# 01-pushbutton_interface.net
KiCad netlist of a schematic drawn in EAGLE
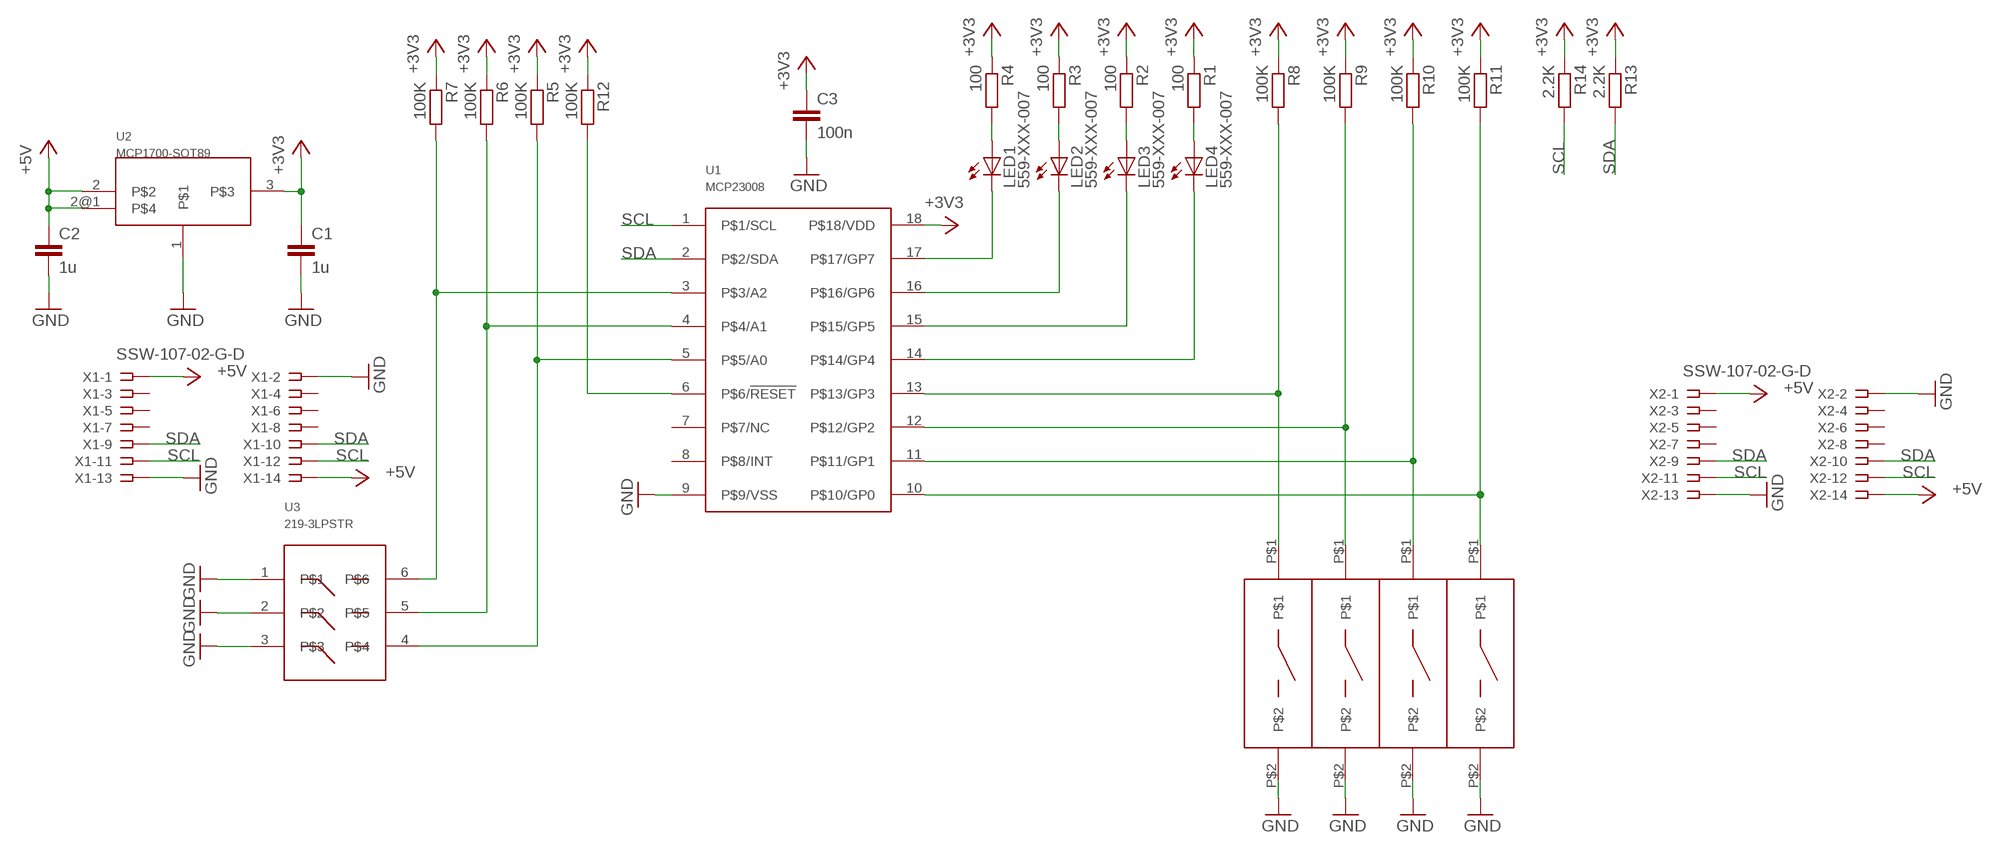
[diagram p0: schematic, sheet 1]

(export (version "E")
  (design (tool "Eeschema 10.0.6"))
  (components
    (comp (ref "C1")
      (value "1u")
      (footprint "eagle-import:C0805")
      (libsource (lib "eagle-import") (part "C-EUC0805"))
    )
    (comp (ref "C2")
      (value "1u")
      (footprint "eagle-import:C0805")
      (libsource (lib "eagle-import") (part "C-EUC0805"))
    )
    (comp (ref "C3")
      (value "100n")
      (footprint "eagle-import:C0805")
      (libsource (lib "eagle-import") (part "C-EUC0805"))
    )
    (comp (ref "LED1")
      (value "559-XXX-007")
      (footprint "eagle-import:LED")
      (libsource (lib "eagle-import") (part "559-XXX-007"))
    )
    (comp (ref "LED2")
      (value "559-XXX-007")
      (footprint "eagle-import:LED")
      (libsource (lib "eagle-import") (part "559-XXX-007"))
    )
    (comp (ref "LED3")
      (value "559-XXX-007")
      (footprint "eagle-import:LED")
      (libsource (lib "eagle-import") (part "559-XXX-007"))
    )
    (comp (ref "LED4")
      (value "559-XXX-007")
      (footprint "eagle-import:LED")
      (libsource (lib "eagle-import") (part "559-XXX-007"))
    )
    (comp (ref "R1")
      (value "100")
      (footprint "eagle-import:R0805")
      (libsource (lib "eagle-import") (part "R-EU_R0805"))
    )
    (comp (ref "R2")
      (value "100")
      (footprint "eagle-import:R0805")
      (libsource (lib "eagle-import") (part "R-EU_R0805"))
    )
    (comp (ref "R3")
      (value "100")
      (footprint "eagle-import:R0805")
      (libsource (lib "eagle-import") (part "R-EU_R0805"))
    )
    (comp (ref "R4")
      (value "100")
      (footprint "eagle-import:R0805")
      (libsource (lib "eagle-import") (part "R-EU_R0805"))
    )
    (comp (ref "R5")
      (value "100K")
      (footprint "eagle-import:R0805")
      (libsource (lib "eagle-import") (part "R-EU_R0805"))
    )
    (comp (ref "R6")
      (value "100K")
      (footprint "eagle-import:R0805")
      (libsource (lib "eagle-import") (part "R-EU_R0805"))
    )
    (comp (ref "R7")
      (value "100K")
      (footprint "eagle-import:R0805")
      (libsource (lib "eagle-import") (part "R-EU_R0805"))
    )
    (comp (ref "R8")
      (value "100K")
      (footprint "eagle-import:R0805")
      (libsource (lib "eagle-import") (part "R-EU_R0805"))
    )
    (comp (ref "R9")
      (value "100K")
      (footprint "eagle-import:R0805")
      (libsource (lib "eagle-import") (part "R-EU_R0805"))
    )
    (comp (ref "R10")
      (value "100K")
      (footprint "eagle-import:R0805")
      (libsource (lib "eagle-import") (part "R-EU_R0805"))
    )
    (comp (ref "R11")
      (value "100K")
      (footprint "eagle-import:R0805")
      (libsource (lib "eagle-import") (part "R-EU_R0805"))
    )
    (comp (ref "R12")
      (value "100K")
      (footprint "eagle-import:R0805")
      (libsource (lib "eagle-import") (part "R-EU_R0805"))
    )
    (comp (ref "R13")
      (value "2.2K")
      (footprint "eagle-import:R0805")
      (libsource (lib "eagle-import") (part "R-EU_R0805"))
    )
    (comp (ref "R14")
      (value "2.2K")
      (footprint "eagle-import:R0805")
      (libsource (lib "eagle-import") (part "R-EU_R0805"))
    )
    (comp (ref "SW1")
      (value "PB-SWITCH")
      (footprint "eagle-import:SWITCH")
      (libsource (lib "eagle-import") (part "PB-SWITCH"))
    )
    (comp (ref "SW2")
      (value "PB-SWITCH")
      (footprint "eagle-import:SWITCH")
      (libsource (lib "eagle-import") (part "PB-SWITCH"))
    )
    (comp (ref "SW3")
      (value "PB-SWITCH")
      (footprint "eagle-import:SWITCH")
      (libsource (lib "eagle-import") (part "PB-SWITCH"))
    )
    (comp (ref "SW4")
      (value "PB-SWITCH")
      (footprint "eagle-import:SWITCH")
      (libsource (lib "eagle-import") (part "PB-SWITCH"))
    )
    (comp (ref "U1")
      (value "MCP23008")
      (footprint "eagle-import:MCP23008-SO18")
      (libsource (lib "eagle-import") (part "MCP23008"))
    )
    (comp (ref "U2")
      (value "MCP1700-SOT89")
      (footprint "eagle-import:MCP1700-SOT89")
      (libsource (lib "eagle-import") (part "MCP1700-SOT89"))
    )
    (comp (ref "U3")
      (value "219-3LPSTR")
      (footprint "eagle-import:219-3LPSTR")
      (libsource (lib "eagle-import") (part "219-3LPSTR"))
    )
    (comp (ref "X1")
      (value "SSW-107-02-G-D")
      (footprint "eagle-import:SSW-107-02-G-D")
      (fields (field (name "MF") "Samtec Inc."))
      (libsource (lib "eagle-import") (part "SSW-107-02-G-D"))
    )
    (comp (ref "X2")
      (value "SSW-107-02-G-D")
      (footprint "eagle-import:SSW-107-02-G-D")
      (fields (field (name "MF") "Samtec Inc."))
      (libsource (lib "eagle-import") (part "SSW-107-02-G-D"))
    )
  )
  (nets
    (net (code "1") (name "+3V3") (class "Default")
      (node (ref "C1") (pin "1") (pinfunction "1_1") (pintype "passive"))
      (node (ref "C3") (pin "1") (pinfunction "1_1") (pintype "passive"))
      (node (ref "R1") (pin "1") (pinfunction "1_1") (pintype "passive"))
      (node (ref "R10") (pin "1") (pinfunction "1_1") (pintype "passive"))
      (node (ref "R11") (pin "1") (pinfunction "1_1") (pintype "passive"))
      (node (ref "R12") (pin "1") (pinfunction "1_1") (pintype "passive"))
      (node (ref "R13") (pin "1") (pinfunction "1_1") (pintype "passive"))
      (node (ref "R14") (pin "1") (pinfunction "1_1") (pintype "passive"))
      (node (ref "R2") (pin "1") (pinfunction "1_1") (pintype "passive"))
      (node (ref "R3") (pin "1") (pinfunction "1_1") (pintype "passive"))
      (node (ref "R4") (pin "1") (pinfunction "1_1") (pintype "passive"))
      (node (ref "R5") (pin "1") (pinfunction "1_1") (pintype "passive"))
      (node (ref "R6") (pin "1") (pinfunction "1_1") (pintype "passive"))
      (node (ref "R7") (pin "1") (pinfunction "1_1") (pintype "passive"))
      (node (ref "R8") (pin "1") (pinfunction "1_1") (pintype "passive"))
      (node (ref "R9") (pin "1") (pinfunction "1_1") (pintype "passive"))
      (node (ref "U1") (pin "18") (pinfunction "P$18/VDD_18") (pintype "bidirectional"))
      (node (ref "U2") (pin "3") (pinfunction "P$3_3") (pintype "bidirectional"))
    )
    (net (code "2") (name "+5V") (class "Default")
      (node (ref "C2") (pin "1") (pinfunction "1_1") (pintype "passive"))
      (node (ref "U2") (pin "2") (pinfunction "P$2_2") (pintype "bidirectional"))
      (node (ref "U2") (pin "2@1") (pinfunction "P$4_2@1") (pintype "bidirectional"))
      (node (ref "X1") (pin "1") (pinfunction "1_1") (pintype "passive"))
      (node (ref "X1") (pin "14") (pinfunction "1_14") (pintype "passive"))
      (node (ref "X2") (pin "1") (pinfunction "1_1") (pintype "passive"))
      (node (ref "X2") (pin "14") (pinfunction "1_14") (pintype "passive"))
    )
    (net (code "3") (name "/SCL") (class "Default")
      (node (ref "R14") (pin "2") (pinfunction "2_2") (pintype "passive"))
      (node (ref "U1") (pin "1") (pinfunction "P$1/SCL_1") (pintype "bidirectional"))
      (node (ref "X1") (pin "11") (pinfunction "1_11") (pintype "passive"))
      (node (ref "X1") (pin "12") (pinfunction "1_12") (pintype "passive"))
      (node (ref "X2") (pin "11") (pinfunction "1_11") (pintype "passive"))
      (node (ref "X2") (pin "12") (pinfunction "1_12") (pintype "passive"))
    )
    (net (code "4") (name "/SDA") (class "Default")
      (node (ref "R13") (pin "2") (pinfunction "2_2") (pintype "passive"))
      (node (ref "U1") (pin "2") (pinfunction "P$2/SDA_2") (pintype "bidirectional"))
      (node (ref "X1") (pin "10") (pinfunction "1_10") (pintype "passive"))
      (node (ref "X1") (pin "9") (pinfunction "1_9") (pintype "passive"))
      (node (ref "X2") (pin "10") (pinfunction "1_10") (pintype "passive"))
      (node (ref "X2") (pin "9") (pinfunction "1_9") (pintype "passive"))
    )
    (net (code "5") (name "GND") (class "Default")
      (node (ref "C1") (pin "2") (pinfunction "2_2") (pintype "passive"))
      (node (ref "C2") (pin "2") (pinfunction "2_2") (pintype "passive"))
      (node (ref "C3") (pin "2") (pinfunction "2_2") (pintype "passive"))
      (node (ref "SW1") (pin "P$2") (pinfunction "P$2_P$2") (pintype "bidirectional"))
      (node (ref "SW2") (pin "P$2") (pinfunction "P$2_P$2") (pintype "bidirectional"))
      (node (ref "SW3") (pin "P$2") (pinfunction "P$2_P$2") (pintype "bidirectional"))
      (node (ref "SW4") (pin "P$2") (pinfunction "P$2_P$2") (pintype "bidirectional"))
      (node (ref "U1") (pin "9") (pinfunction "P$9/VSS_9") (pintype "bidirectional"))
      (node (ref "U2") (pin "1") (pinfunction "P$1_1") (pintype "bidirectional"))
      (node (ref "U3") (pin "1") (pinfunction "P$1_1") (pintype "bidirectional"))
      (node (ref "U3") (pin "2") (pinfunction "P$2_2") (pintype "bidirectional"))
      (node (ref "U3") (pin "3") (pinfunction "P$3_3") (pintype "bidirectional"))
      (node (ref "X1") (pin "13") (pinfunction "1_13") (pintype "passive"))
      (node (ref "X1") (pin "2") (pinfunction "1_2") (pintype "passive"))
      (node (ref "X2") (pin "13") (pinfunction "1_13") (pintype "passive"))
      (node (ref "X2") (pin "2") (pinfunction "1_2") (pintype "passive"))
    )
    (net (code "6") (name "Net-(LED1-A)") (class "Default")
      (node (ref "LED1") (pin "P$1") (pinfunction "A_P$1") (pintype "passive"))
      (node (ref "R4") (pin "2") (pinfunction "2_2") (pintype "passive"))
    )
    (net (code "7") (name "Net-(LED1-C)") (class "Default")
      (node (ref "LED1") (pin "P$2") (pinfunction "C_P$2") (pintype "passive"))
      (node (ref "U1") (pin "17") (pinfunction "P$17/GP7_17") (pintype "bidirectional"))
    )
    (net (code "8") (name "Net-(LED2-A)") (class "Default")
      (node (ref "LED2") (pin "P$1") (pinfunction "A_P$1") (pintype "passive"))
      (node (ref "R3") (pin "2") (pinfunction "2_2") (pintype "passive"))
    )
    (net (code "9") (name "Net-(LED2-C)") (class "Default")
      (node (ref "LED2") (pin "P$2") (pinfunction "C_P$2") (pintype "passive"))
      (node (ref "U1") (pin "16") (pinfunction "P$16/GP6_16") (pintype "bidirectional"))
    )
    (net (code "10") (name "Net-(LED3-A)") (class "Default")
      (node (ref "LED3") (pin "P$1") (pinfunction "A_P$1") (pintype "passive"))
      (node (ref "R2") (pin "2") (pinfunction "2_2") (pintype "passive"))
    )
    (net (code "11") (name "Net-(LED3-C)") (class "Default")
      (node (ref "LED3") (pin "P$2") (pinfunction "C_P$2") (pintype "passive"))
      (node (ref "U1") (pin "15") (pinfunction "P$15/GP5_15") (pintype "bidirectional"))
    )
    (net (code "12") (name "Net-(LED4-A)") (class "Default")
      (node (ref "LED4") (pin "P$1") (pinfunction "A_P$1") (pintype "passive"))
      (node (ref "R1") (pin "2") (pinfunction "2_2") (pintype "passive"))
    )
    (net (code "13") (name "Net-(LED4-C)") (class "Default")
      (node (ref "LED4") (pin "P$2") (pinfunction "C_P$2") (pintype "passive"))
      (node (ref "U1") (pin "14") (pinfunction "P$14/GP4_14") (pintype "bidirectional"))
    )
    (net (code "14") (name "Net-(U1-P$3{slash}A2)") (class "Default")
      (node (ref "R7") (pin "2") (pinfunction "2_2") (pintype "passive"))
      (node (ref "U1") (pin "3") (pinfunction "P$3/A2_3") (pintype "bidirectional"))
      (node (ref "U3") (pin "6") (pinfunction "P$6_6") (pintype "bidirectional"))
    )
    (net (code "15") (name "Net-(U1-P$4{slash}A1)") (class "Default")
      (node (ref "R6") (pin "2") (pinfunction "2_2") (pintype "passive"))
      (node (ref "U1") (pin "4") (pinfunction "P$4/A1_4") (pintype "bidirectional"))
      (node (ref "U3") (pin "5") (pinfunction "P$5_5") (pintype "bidirectional"))
    )
    (net (code "16") (name "Net-(U1-P$5{slash}A0)") (class "Default")
      (node (ref "R5") (pin "2") (pinfunction "2_2") (pintype "passive"))
      (node (ref "U1") (pin "5") (pinfunction "P$5/A0_5") (pintype "bidirectional"))
      (node (ref "U3") (pin "4") (pinfunction "P$4_4") (pintype "bidirectional"))
    )
    (net (code "17") (name "Net-(U1-P$6{slash}~{RESET})") (class "Default")
      (node (ref "R12") (pin "2") (pinfunction "2_2") (pintype "passive"))
      (node (ref "U1") (pin "6") (pinfunction "P$6/~{RESET}_6") (pintype "bidirectional"))
    )
    (net (code "18") (name "Net-(U1-P$10{slash}GP0)") (class "Default")
      (node (ref "R11") (pin "2") (pinfunction "2_2") (pintype "passive"))
      (node (ref "SW4") (pin "P$1") (pinfunction "P$1_P$1") (pintype "bidirectional"))
      (node (ref "U1") (pin "10") (pinfunction "P$10/GP0_10") (pintype "bidirectional"))
    )
    (net (code "19") (name "Net-(U1-P$11{slash}GP1)") (class "Default")
      (node (ref "R10") (pin "2") (pinfunction "2_2") (pintype "passive"))
      (node (ref "SW3") (pin "P$1") (pinfunction "P$1_P$1") (pintype "bidirectional"))
      (node (ref "U1") (pin "11") (pinfunction "P$11/GP1_11") (pintype "bidirectional"))
    )
    (net (code "20") (name "Net-(U1-P$12{slash}GP2)") (class "Default")
      (node (ref "R9") (pin "2") (pinfunction "2_2") (pintype "passive"))
      (node (ref "SW2") (pin "P$1") (pinfunction "P$1_P$1") (pintype "bidirectional"))
      (node (ref "U1") (pin "12") (pinfunction "P$12/GP2_12") (pintype "bidirectional"))
    )
    (net (code "21") (name "Net-(U1-P$13{slash}GP3)") (class "Default")
      (node (ref "R8") (pin "2") (pinfunction "2_2") (pintype "passive"))
      (node (ref "SW1") (pin "P$1") (pinfunction "P$1_P$1") (pintype "bidirectional"))
      (node (ref "U1") (pin "13") (pinfunction "P$13/GP3_13") (pintype "bidirectional"))
    )
    (net (code "22") (name "unconnected-(U1-P$7{slash}NC-Pad7)") (class "Default")
      (node (ref "U1") (pin "7") (pinfunction "P$7/NC_7") (pintype "bidirectional"))
    )
    (net (code "23") (name "unconnected-(U1-P$8{slash}INT-Pad8)") (class "Default")
      (node (ref "U1") (pin "8") (pinfunction "P$8/INT_8") (pintype "bidirectional"))
    )
    (net (code "24") (name "unconnected-(X1H-1-Pad3)") (class "Default")
      (node (ref "X1") (pin "3") (pinfunction "1_3") (pintype "passive"))
    )
    (net (code "25") (name "unconnected-(X1I-1-Pad4)") (class "Default")
      (node (ref "X1") (pin "4") (pinfunction "1_4") (pintype "passive"))
    )
    (net (code "26") (name "unconnected-(X1J-1-Pad5)") (class "Default")
      (node (ref "X1") (pin "5") (pinfunction "1_5") (pintype "passive"))
    )
    (net (code "27") (name "unconnected-(X1K-1-Pad6)") (class "Default")
      (node (ref "X1") (pin "6") (pinfunction "1_6") (pintype "passive"))
    )
    (net (code "28") (name "unconnected-(X1L-1-Pad7)") (class "Default")
      (node (ref "X1") (pin "7") (pinfunction "1_7") (pintype "passive"))
    )
    (net (code "29") (name "unconnected-(X1M-1-Pad8)") (class "Default")
      (node (ref "X1") (pin "8") (pinfunction "1_8") (pintype "passive"))
    )
    (net (code "30") (name "unconnected-(X2H-1-Pad3)") (class "Default")
      (node (ref "X2") (pin "3") (pinfunction "1_3") (pintype "passive"))
    )
    (net (code "31") (name "unconnected-(X2I-1-Pad4)") (class "Default")
      (node (ref "X2") (pin "4") (pinfunction "1_4") (pintype "passive"))
    )
    (net (code "32") (name "unconnected-(X2J-1-Pad5)") (class "Default")
      (node (ref "X2") (pin "5") (pinfunction "1_5") (pintype "passive"))
    )
    (net (code "33") (name "unconnected-(X2K-1-Pad6)") (class "Default")
      (node (ref "X2") (pin "6") (pinfunction "1_6") (pintype "passive"))
    )
    (net (code "34") (name "unconnected-(X2L-1-Pad7)") (class "Default")
      (node (ref "X2") (pin "7") (pinfunction "1_7") (pintype "passive"))
    )
    (net (code "35") (name "unconnected-(X2M-1-Pad8)") (class "Default")
      (node (ref "X2") (pin "8") (pinfunction "1_8") (pintype "passive"))
    )
  )
)
